# 5VAC_TO_DC.net
KiCad netlist of a schematic drawn in EAGLE
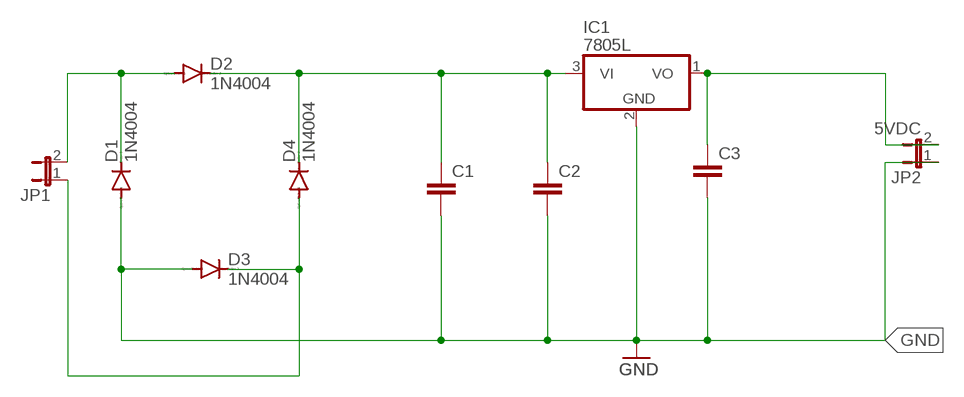
[diagram p0: schematic, sheet 1]

(export (version "E")
  (design (tool "Eeschema 10.0.6"))
  (components
    (comp (ref "C1")
      (value "C2,5-3")
      (footprint "eagle-import:C2.5-3")
      (libsource (lib "eagle-import") (part "C2,5-3"))
    )
    (comp (ref "C2")
      (value "C2,5-3")
      (footprint "eagle-import:C2.5-3")
      (libsource (lib "eagle-import") (part "C2,5-3"))
    )
    (comp (ref "C3")
      (value "C2,5-3")
      (footprint "eagle-import:C2.5-3")
      (libsource (lib "eagle-import") (part "C2,5-3"))
    )
    (comp (ref "D1")
      (value "1N4004")
      (footprint "eagle-import:DO41-10")
      (libsource (lib "eagle-import") (part "1N4004"))
    )
    (comp (ref "D2")
      (value "1N4004")
      (footprint "eagle-import:DO41-10")
      (libsource (lib "eagle-import") (part "1N4004"))
    )
    (comp (ref "D3")
      (value "1N4004")
      (footprint "eagle-import:DO41-10")
      (libsource (lib "eagle-import") (part "1N4004"))
    )
    (comp (ref "D4")
      (value "1N4004")
      (footprint "eagle-import:DO41-10")
      (libsource (lib "eagle-import") (part "1N4004"))
    )
    (comp (ref "IC1")
      (value "7805L")
      (footprint "eagle-import:TO92")
      (libsource (lib "eagle-import") (part "78L05"))
    )
    (comp (ref "JP1")
      (value "JP1E")
      (footprint "eagle-import:JP1")
      (libsource (lib "eagle-import") (part "JP1E"))
    )
    (comp (ref "JP2")
      (value "5VDC")
      (footprint "eagle-import:JP1")
      (libsource (lib "eagle-import") (part "JP1E"))
    )
  )
  (nets
    (net (code "1") (name "GND") (class "Default")
      (node (ref "C1") (pin "2") (pinfunction "2_2") (pintype "passive"))
      (node (ref "C2") (pin "2") (pinfunction "2_2") (pintype "passive"))
      (node (ref "C3") (pin "2") (pinfunction "2_2") (pintype "passive"))
      (node (ref "D1") (pin "A") (pinfunction "A_A") (pintype "passive"))
      (node (ref "D3") (pin "A") (pinfunction "A_A") (pintype "passive"))
      (node (ref "IC1") (pin "2") (pinfunction "GND_2") (pintype "passive"))
      (node (ref "JP2") (pin "1") (pinfunction "1_1") (pintype "passive"))
    )
    (net (code "2") (name "Net-(D1-PadC)") (class "Default")
      (node (ref "D1") (pin "C") (pinfunction "C_C") (pintype "passive"))
      (node (ref "D2") (pin "A") (pinfunction "A_A") (pintype "passive"))
      (node (ref "JP1") (pin "2") (pinfunction "2_2") (pintype "passive"))
    )
    (net (code "3") (name "Net-(D3-PadC)") (class "Default")
      (node (ref "D3") (pin "C") (pinfunction "C_C") (pintype "passive"))
      (node (ref "D4") (pin "A") (pinfunction "A_A") (pintype "passive"))
      (node (ref "JP1") (pin "1") (pinfunction "1_1") (pintype "passive"))
    )
    (net (code "4") (name "Net-(IC1-VI)") (class "Default")
      (node (ref "C1") (pin "1") (pinfunction "1_1") (pintype "passive"))
      (node (ref "C2") (pin "1") (pinfunction "1_1") (pintype "passive"))
      (node (ref "D2") (pin "C") (pinfunction "C_C") (pintype "passive"))
      (node (ref "D4") (pin "C") (pinfunction "C_C") (pintype "passive"))
      (node (ref "IC1") (pin "3") (pinfunction "VI_3") (pintype "input"))
    )
    (net (code "5") (name "Net-(IC1-VO)") (class "Default")
      (node (ref "C3") (pin "1") (pinfunction "1_1") (pintype "passive"))
      (node (ref "IC1") (pin "1") (pinfunction "VO_1") (pintype "passive"))
      (node (ref "JP2") (pin "2") (pinfunction "2_2") (pintype "passive"))
    )
  )
)
